# DAC_DAC8565.net
KiCad netlist of a schematic drawn in EAGLE
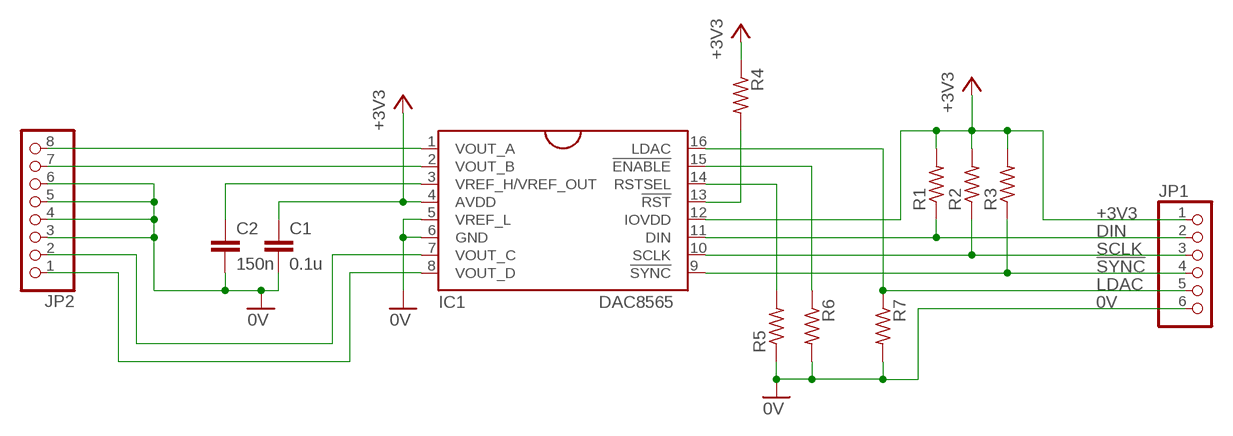
[diagram p0: schematic, sheet 1]

(export (version "E")
  (design (tool "Eeschema 10.0.6"))
  (components
    (comp (ref "C1")
      (value "0.1u")
      (footprint "eagle-import:C1206")
      (libsource (lib "eagle-import") (part "C-EUC1206"))
    )
    (comp (ref "C2")
      (value "150n")
      (footprint "eagle-import:C1206")
      (libsource (lib "eagle-import") (part "C-EUC1206"))
    )
    (comp (ref "IC1")
      (value "DAC8565")
      (footprint "eagle-import:TSSOP-16")
      (libsource (lib "eagle-import") (part "DAC8565"))
    )
    (comp (ref "JP1")
      (value "PINHD-1X6")
      (footprint "eagle-import:1X06")
      (libsource (lib "eagle-import") (part "PINHD-1X6"))
    )
    (comp (ref "JP2")
      (value "PINHD-1X8")
      (footprint "eagle-import:1X08")
      (libsource (lib "eagle-import") (part "PINHD-1X8"))
    )
    (comp (ref "R1")
      (value "R-US_R0805")
      (footprint "eagle-import:R0805")
      (libsource (lib "eagle-import") (part "R-US_R0805"))
    )
    (comp (ref "R2")
      (value "R-US_R0805")
      (footprint "eagle-import:R0805")
      (libsource (lib "eagle-import") (part "R-US_R0805"))
    )
    (comp (ref "R3")
      (value "R-US_R0805")
      (footprint "eagle-import:R0805")
      (libsource (lib "eagle-import") (part "R-US_R0805"))
    )
    (comp (ref "R4")
      (value "R-US_R0805")
      (footprint "eagle-import:R0805")
      (libsource (lib "eagle-import") (part "R-US_R0805"))
    )
    (comp (ref "R5")
      (value "R-US_R0805")
      (footprint "eagle-import:R0805")
      (libsource (lib "eagle-import") (part "R-US_R0805"))
    )
    (comp (ref "R6")
      (value "R-US_0204/7")
      (footprint "eagle-import:0204_7")
      (libsource (lib "eagle-import") (part "R-US_0204/7"))
    )
    (comp (ref "R7")
      (value "R-US_R0805")
      (footprint "eagle-import:R0805")
      (libsource (lib "eagle-import") (part "R-US_R0805"))
    )
  )
  (nets
    (net (code "1") (name "+3V3") (class "Default")
      (node (ref "C1") (pin "1") (pinfunction "1_1") (pintype "passive"))
      (node (ref "IC1") (pin "12") (pinfunction "IOVDD_12") (pintype "bidirectional"))
      (node (ref "IC1") (pin "4") (pinfunction "AVDD_4") (pintype "bidirectional"))
      (node (ref "JP1") (pin "1") (pinfunction "1_1") (pintype "passive"))
      (node (ref "R1") (pin "2") (pinfunction "2_2") (pintype "passive"))
      (node (ref "R2") (pin "2") (pinfunction "2_2") (pintype "passive"))
      (node (ref "R3") (pin "2") (pinfunction "2_2") (pintype "passive"))
      (node (ref "R4") (pin "1") (pinfunction "1_1") (pintype "passive"))
    )
    (net (code "2") (name "/DIN") (class "Default")
      (node (ref "IC1") (pin "11") (pinfunction "DIN_11") (pintype "bidirectional"))
      (node (ref "JP1") (pin "2") (pinfunction "2_2") (pintype "passive"))
      (node (ref "R1") (pin "1") (pinfunction "1_1") (pintype "passive"))
    )
    (net (code "3") (name "/LDAC") (class "Default")
      (node (ref "IC1") (pin "16") (pinfunction "LDAC_16") (pintype "bidirectional"))
      (node (ref "JP1") (pin "5") (pinfunction "5_5") (pintype "passive"))
      (node (ref "R7") (pin "1") (pinfunction "1_1") (pintype "passive"))
    )
    (net (code "4") (name "/SCLK") (class "Default")
      (node (ref "IC1") (pin "10") (pinfunction "SCLK_10") (pintype "bidirectional"))
      (node (ref "JP1") (pin "3") (pinfunction "3_3") (pintype "passive"))
      (node (ref "R2") (pin "1") (pinfunction "1_1") (pintype "passive"))
    )
    (net (code "5") (name "/~{SYNC}") (class "Default")
      (node (ref "IC1") (pin "9") (pinfunction "~{SYNC}_9") (pintype "bidirectional"))
      (node (ref "JP1") (pin "4") (pinfunction "4_4") (pintype "passive"))
      (node (ref "R3") (pin "1") (pinfunction "1_1") (pintype "passive"))
    )
    (net (code "6") (name "0V") (class "Default")
      (node (ref "C1") (pin "2") (pinfunction "2_2") (pintype "passive"))
      (node (ref "C2") (pin "2") (pinfunction "2_2") (pintype "passive"))
      (node (ref "IC1") (pin "5") (pinfunction "VREF_L_5") (pintype "bidirectional"))
      (node (ref "IC1") (pin "6") (pinfunction "GND_6") (pintype "bidirectional"))
      (node (ref "JP1") (pin "6") (pinfunction "6_6") (pintype "passive"))
      (node (ref "JP2") (pin "3") (pinfunction "3_3") (pintype "passive"))
      (node (ref "JP2") (pin "4") (pinfunction "4_4") (pintype "passive"))
      (node (ref "JP2") (pin "5") (pinfunction "5_5") (pintype "passive"))
      (node (ref "JP2") (pin "6") (pinfunction "6_6") (pintype "passive"))
      (node (ref "R5") (pin "1") (pinfunction "1_1") (pintype "passive"))
      (node (ref "R6") (pin "2") (pinfunction "2_2") (pintype "passive"))
      (node (ref "R7") (pin "2") (pinfunction "2_2") (pintype "passive"))
    )
    (net (code "7") (name "Net-(IC1-RSTSEL)") (class "Default")
      (node (ref "IC1") (pin "14") (pinfunction "RSTSEL_14") (pintype "bidirectional"))
      (node (ref "R5") (pin "2") (pinfunction "2_2") (pintype "passive"))
    )
    (net (code "8") (name "Net-(IC1-VOUT_A)") (class "Default")
      (node (ref "IC1") (pin "1") (pinfunction "VOUT_A_1") (pintype "bidirectional"))
      (node (ref "JP2") (pin "8") (pinfunction "8_8") (pintype "passive"))
    )
    (net (code "9") (name "Net-(IC1-VOUT_B)") (class "Default")
      (node (ref "IC1") (pin "2") (pinfunction "VOUT_B_2") (pintype "bidirectional"))
      (node (ref "JP2") (pin "7") (pinfunction "7_7") (pintype "passive"))
    )
    (net (code "10") (name "Net-(IC1-VOUT_C)") (class "Default")
      (node (ref "IC1") (pin "7") (pinfunction "VOUT_C_7") (pintype "bidirectional"))
      (node (ref "JP2") (pin "2") (pinfunction "2_2") (pintype "passive"))
    )
    (net (code "11") (name "Net-(IC1-VOUT_D)") (class "Default")
      (node (ref "IC1") (pin "8") (pinfunction "VOUT_D_8") (pintype "bidirectional"))
      (node (ref "JP2") (pin "1") (pinfunction "1_1") (pintype "passive"))
    )
    (net (code "12") (name "Net-(IC1-VREF_H{slash}VREF_OUT)") (class "Default")
      (node (ref "C2") (pin "1") (pinfunction "1_1") (pintype "passive"))
      (node (ref "IC1") (pin "3") (pinfunction "VREF_H/VREF_OUT_3") (pintype "bidirectional"))
    )
    (net (code "13") (name "Net-(IC1-~{ENABLE})") (class "Default")
      (node (ref "IC1") (pin "15") (pinfunction "~{ENABLE}_15") (pintype "bidirectional"))
      (node (ref "R6") (pin "1") (pinfunction "1_1") (pintype "passive"))
    )
    (net (code "14") (name "Net-(IC1-~{RST})") (class "Default")
      (node (ref "IC1") (pin "13") (pinfunction "~{RST}_13") (pintype "bidirectional"))
      (node (ref "R4") (pin "2") (pinfunction "2_2") (pintype "passive"))
    )
  )
)
